# MineSweepers2019-Board.net
KiCad netlist of a schematic drawn in EAGLE
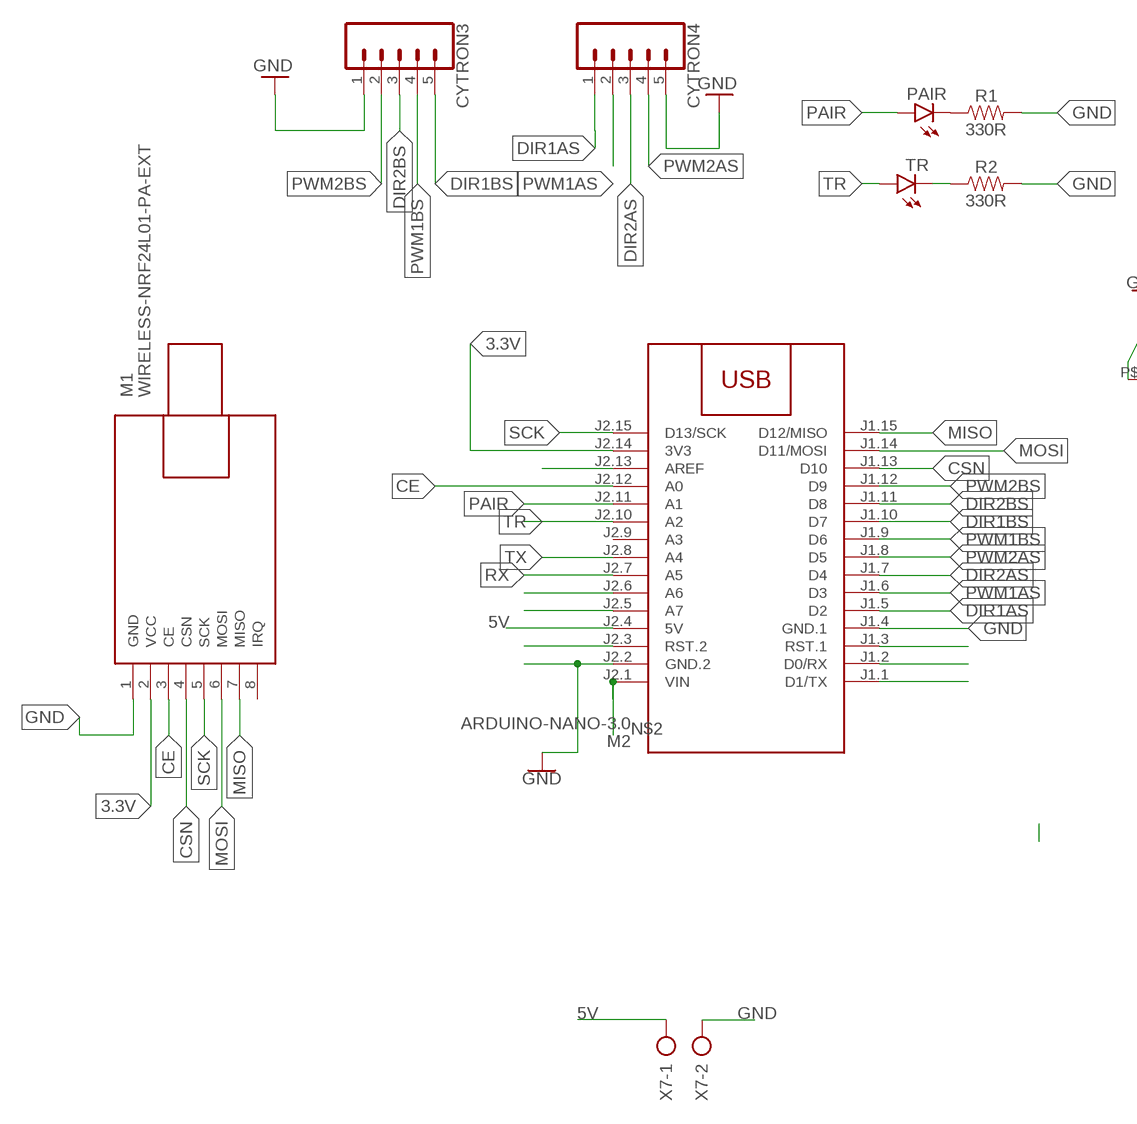
[diagram p0: schematic, sheet 1, part 1 of 2]
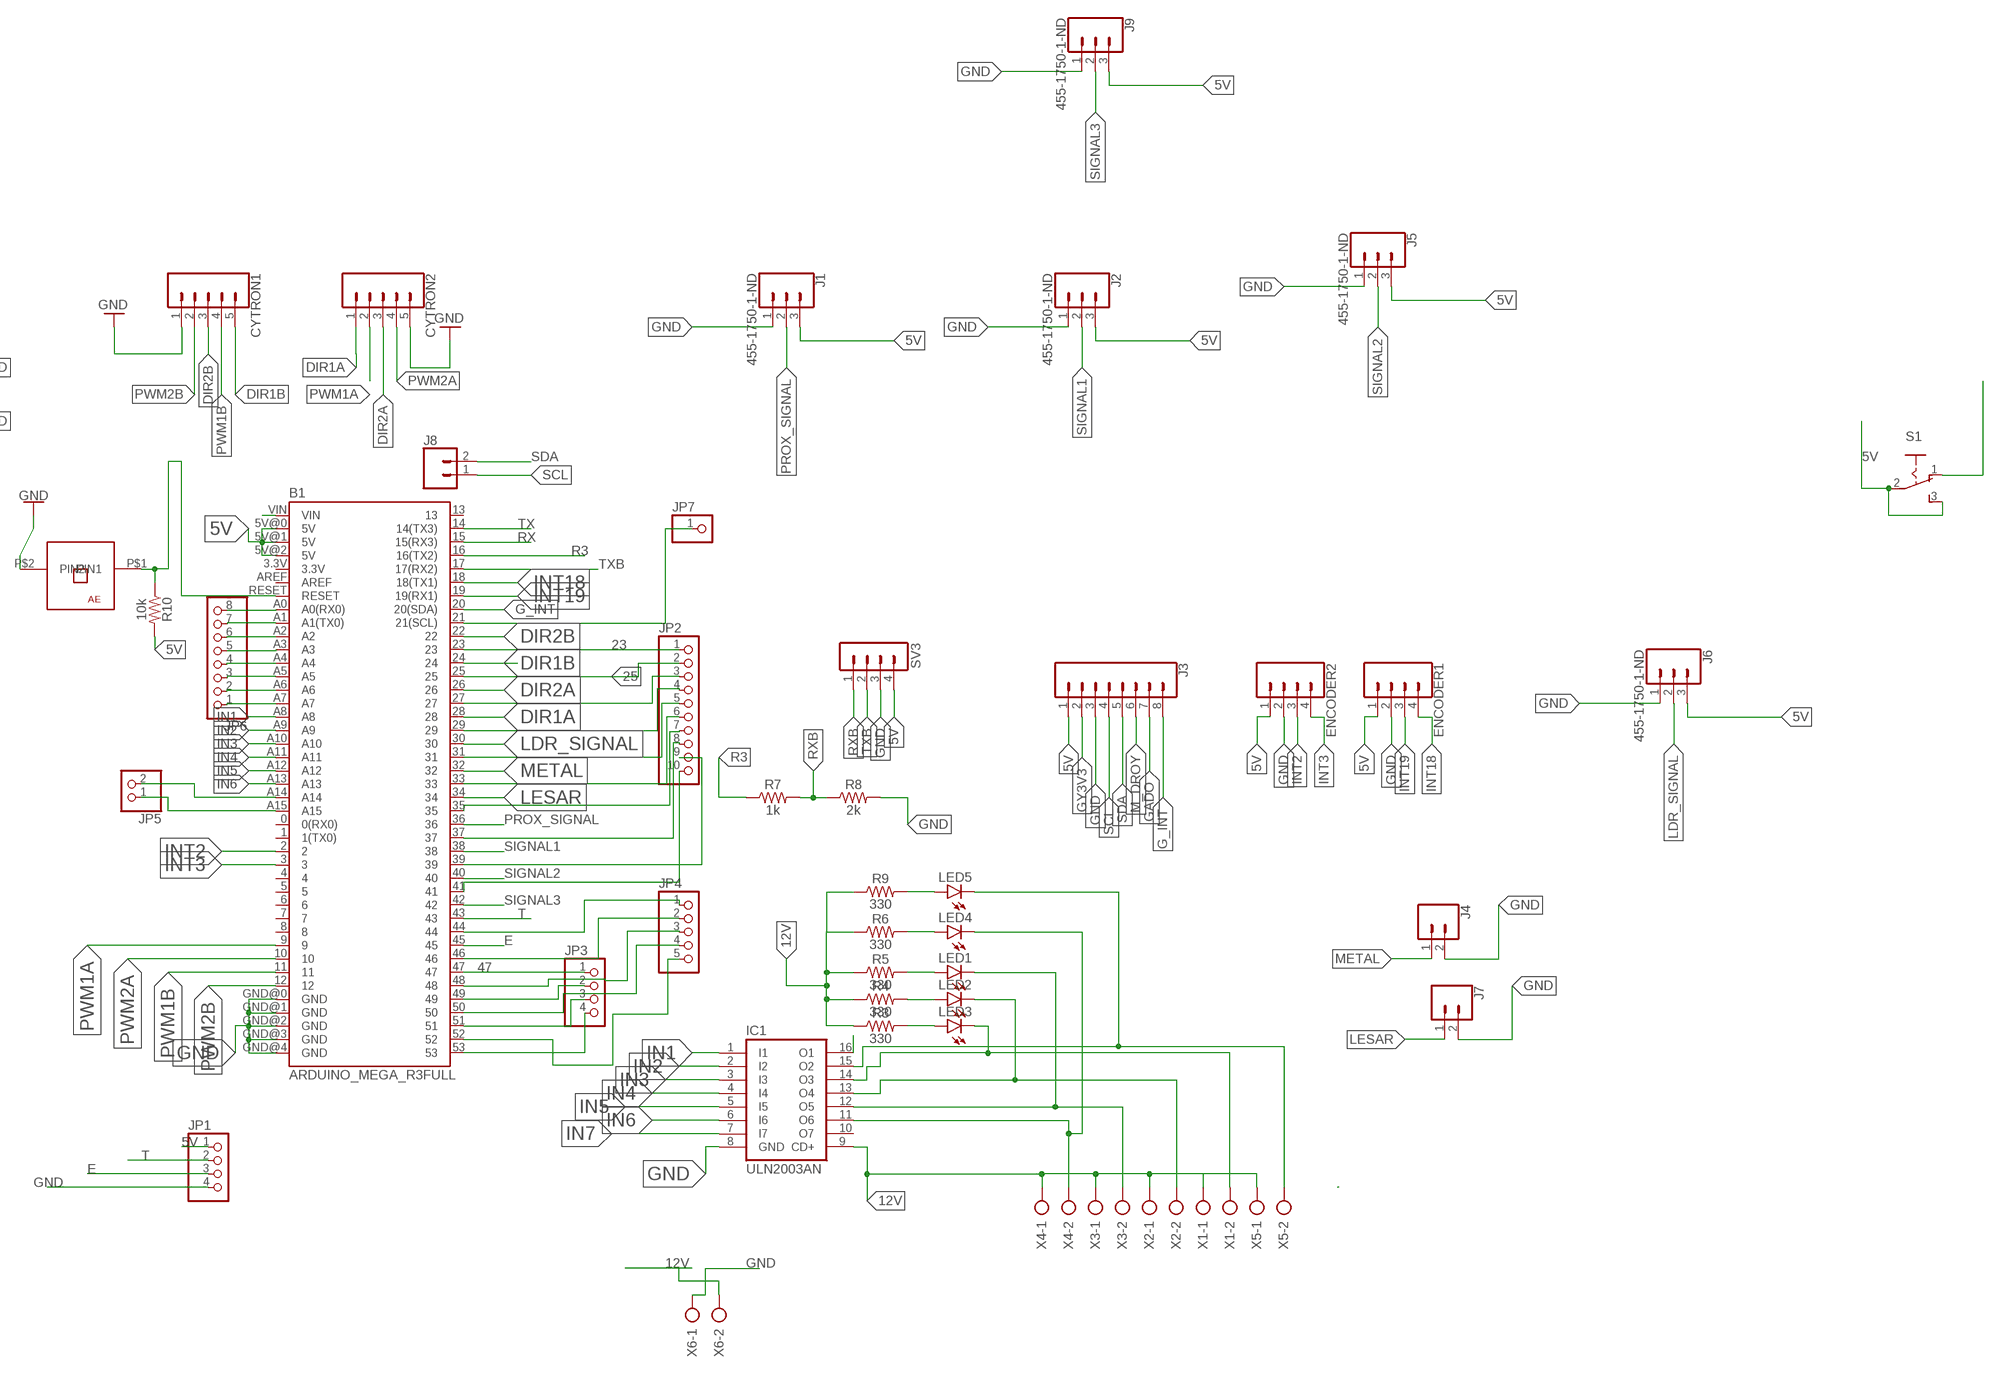
[diagram p1: schematic, sheet 1, part 2 of 2]

(export (version "E")
  (design (tool "Eeschema 10.0.6"))
  (components
    (comp (ref "B1")
      (value "ARDUINO_MEGA_R3FULL")
      (footprint "eagle-import:ARDUINO_MEGA")
      (libsource (lib "eagle-import") (part "ARDUINO_MEGA_R3FULL"))
    )
    (comp (ref "CYTRON1")
      (value "CONN_05")
      (footprint "eagle-import:1X05")
      (libsource (lib "eagle-import") (part "CONN_05"))
    )
    (comp (ref "CYTRON2")
      (value "CONN_05")
      (footprint "eagle-import:1X05")
      (libsource (lib "eagle-import") (part "CONN_05"))
    )
    (comp (ref "CYTRON3")
      (value "CONN_05")
      (footprint "eagle-import:1X05")
      (libsource (lib "eagle-import") (part "CONN_05"))
    )
    (comp (ref "CYTRON4")
      (value "CONN_05")
      (footprint "eagle-import:1X05")
      (libsource (lib "eagle-import") (part "CONN_05"))
    )
    (comp (ref "ENCODER1")
      (value "CONN_04")
      (footprint "eagle-import:1X04")
      (libsource (lib "eagle-import") (part "CONN_04"))
    )
    (comp (ref "ENCODER2")
      (value "CONN_04")
      (footprint "eagle-import:1X04")
      (libsource (lib "eagle-import") (part "CONN_04"))
    )
    (comp (ref "IC1")
      (value "ULN2003AN")
      (footprint "eagle-import:DIL16")
      (libsource (lib "eagle-import") (part "ULN2003AN"))
    )
    (comp (ref "J1")
      (value "455-1750-1-ND")
      (footprint "eagle-import:1X03")
      (libsource (lib "eagle-import") (part "CONN_03"))
    )
    (comp (ref "J2")
      (value "455-1750-1-ND")
      (footprint "eagle-import:1X03")
      (libsource (lib "eagle-import") (part "CONN_03"))
    )
    (comp (ref "J3")
      (value "CONN_08\"")
      (footprint "eagle-import:1X08")
      (libsource (lib "eagle-import") (part "CONN_08{dblquote}"))
    )
    (comp (ref "J4")
      (value "CONN_02")
      (footprint "eagle-import:1X02")
      (libsource (lib "eagle-import") (part "CONN_02"))
    )
    (comp (ref "J5")
      (value "455-1750-1-ND")
      (footprint "eagle-import:1X03")
      (libsource (lib "eagle-import") (part "CONN_03"))
    )
    (comp (ref "J6")
      (value "455-1750-1-ND")
      (footprint "eagle-import:1X03")
      (libsource (lib "eagle-import") (part "CONN_03"))
    )
    (comp (ref "J7")
      (value "CONN_02")
      (footprint "eagle-import:1X02")
      (libsource (lib "eagle-import") (part "CONN_02"))
    )
    (comp (ref "J8")
      (value "CONN_02")
      (footprint "eagle-import:1X02")
      (libsource (lib "eagle-import") (part "CONN_02"))
    )
    (comp (ref "J9")
      (value "455-1750-1-ND")
      (footprint "eagle-import:1X03")
      (libsource (lib "eagle-import") (part "CONN_03"))
    )
    (comp (ref "JP1")
      (value "PINHD-1X4")
      (footprint "eagle-import:1X04")
      (libsource (lib "eagle-import") (part "PINHD-1X4"))
    )
    (comp (ref "JP2")
      (value "PINHD-1X10")
      (footprint "eagle-import:1X10")
      (libsource (lib "eagle-import") (part "PINHD-1X10"))
    )
    (comp (ref "JP3")
      (value "PINHD-1X4")
      (footprint "eagle-import:1X04")
      (libsource (lib "eagle-import") (part "PINHD-1X4"))
    )
    (comp (ref "JP4")
      (value "PINHD-1X5")
      (footprint "eagle-import:1X05")
      (libsource (lib "eagle-import") (part "PINHD-1X5"))
    )
    (comp (ref "JP5")
      (value "PINHD-1X2")
      (footprint "eagle-import:1X02")
      (libsource (lib "eagle-import") (part "PINHD-1X2"))
    )
    (comp (ref "JP6")
      (value "PINHD-1X8")
      (footprint "eagle-import:1X08")
      (libsource (lib "eagle-import") (part "PINHD-1X8"))
    )
    (comp (ref "JP7")
      (value "PINHD-1X1")
      (footprint "eagle-import:1X01")
      (libsource (lib "eagle-import") (part "PINHD-1X1"))
    )
    (comp (ref "LED1")
      (value "LED3MM")
      (footprint "eagle-import:LED3MM")
      (libsource (lib "eagle-import") (part "LED3MM"))
    )
    (comp (ref "LED2")
      (value "LED3MM")
      (footprint "eagle-import:LED3MM")
      (libsource (lib "eagle-import") (part "LED3MM"))
    )
    (comp (ref "LED3")
      (value "LED3MM")
      (footprint "eagle-import:LED3MM")
      (libsource (lib "eagle-import") (part "LED3MM"))
    )
    (comp (ref "LED4")
      (value "LED3MM")
      (footprint "eagle-import:LED3MM")
      (libsource (lib "eagle-import") (part "LED3MM"))
    )
    (comp (ref "LED5")
      (value "LED3MM")
      (footprint "eagle-import:LED3MM")
      (libsource (lib "eagle-import") (part "LED3MM"))
    )
    (comp (ref "M1")
      (value "WIRELESS-NRF24L01-PA-EXT")
      (footprint "eagle-import:WIRELESS-NRF24L01-PA-EXT")
      (libsource (lib "eagle-import") (part "WIRELESS-NRF24L01-PA-EXT"))
    )
    (comp (ref "M2")
      (value "ARDUINO-NANO-3.0")
      (footprint "eagle-import:ARDUINO-NANO-3.0")
      (libsource (lib "eagle-import") (part "ARDUINO-NANO-3.0"))
    )
    (comp (ref "PAIR")
      (value "LED3MM")
      (footprint "eagle-import:LED3MM")
      (libsource (lib "eagle-import") (part "LED3MM"))
    )
    (comp (ref "R1")
      (value "330R")
      (footprint "eagle-import:AXIAL-0.3")
      (libsource (lib "eagle-import") (part "10MOHM-HORIZ-1/4W-5%"))
    )
    (comp (ref "R2")
      (value "330R")
      (footprint "eagle-import:AXIAL-0.3")
      (libsource (lib "eagle-import") (part "10MOHM-HORIZ-1/4W-5%"))
    )
    (comp (ref "R3")
      (value "330")
      (footprint "eagle-import:AXIAL-0.3")
      (libsource (lib "eagle-import") (part "10MOHM-HORIZ-1/4W-5%"))
    )
    (comp (ref "R4")
      (value "330")
      (footprint "eagle-import:AXIAL-0.3")
      (libsource (lib "eagle-import") (part "10MOHM-HORIZ-1/4W-5%"))
    )
    (comp (ref "R5")
      (value "330")
      (footprint "eagle-import:AXIAL-0.3")
      (libsource (lib "eagle-import") (part "10MOHM-HORIZ-1/4W-5%"))
    )
    (comp (ref "R6")
      (value "330")
      (footprint "eagle-import:AXIAL-0.3")
      (libsource (lib "eagle-import") (part "10MOHM-HORIZ-1/4W-5%"))
    )
    (comp (ref "R7")
      (value "1k")
      (footprint "eagle-import:AXIAL-0.3")
      (libsource (lib "eagle-import") (part "10MOHM-HORIZ-1/4W-5%"))
    )
    (comp (ref "R8")
      (value "2k")
      (footprint "eagle-import:AXIAL-0.3")
      (libsource (lib "eagle-import") (part "10MOHM-HORIZ-1/4W-5%"))
    )
    (comp (ref "R9")
      (value "330")
      (footprint "eagle-import:AXIAL-0.3")
      (libsource (lib "eagle-import") (part "10MOHM-HORIZ-1/4W-5%"))
    )
    (comp (ref "R10")
      (value "10k")
      (footprint "eagle-import:AXIAL-0.3")
      (libsource (lib "eagle-import") (part "10MOHM-HORIZ-1/4W-5%"))
    )
    (comp (ref "S1")
      (value "255SB")
      (footprint "eagle-import:255SB")
      (libsource (lib "eagle-import") (part "255SB"))
    )
    (comp (ref "SV3")
      (value "MA04-1")
      (footprint "eagle-import:MA04-1")
      (libsource (lib "eagle-import") (part "MA04-1"))
    )
    (comp (ref "TR")
      (value "LED3MM")
      (footprint "eagle-import:LED3MM")
      (libsource (lib "eagle-import") (part "LED3MM"))
    )
    (comp (ref "U$1")
      (value "PUSHBUTTON-AE")
      (footprint "eagle-import:PUSHBUTTON-AE")
      (libsource (lib "eagle-import") (part "PUSHBUTTON-AE"))
    )
    (comp (ref "X1")
      (value "AK500/2-H")
      (footprint "eagle-import:AK500_2-H")
      (libsource (lib "eagle-import") (part "AK500/2-H"))
    )
    (comp (ref "X2")
      (value "AK500/2-H")
      (footprint "eagle-import:AK500_2-H")
      (libsource (lib "eagle-import") (part "AK500/2-H"))
    )
    (comp (ref "X3")
      (value "AK500/2-H")
      (footprint "eagle-import:AK500_2-H")
      (libsource (lib "eagle-import") (part "AK500/2-H"))
    )
    (comp (ref "X4")
      (value "AK500/2-H")
      (footprint "eagle-import:AK500_2-H")
      (libsource (lib "eagle-import") (part "AK500/2-H"))
    )
    (comp (ref "X5")
      (value "AK500/2-H")
      (footprint "eagle-import:AK500_2-H")
      (libsource (lib "eagle-import") (part "AK500/2-H"))
    )
    (comp (ref "X6")
      (value "AK500/2-H")
      (footprint "eagle-import:AK500_2-H")
      (libsource (lib "eagle-import") (part "AK500/2-H"))
    )
    (comp (ref "X7")
      (value "AK500/2-H")
      (footprint "eagle-import:AK500_2-H")
      (libsource (lib "eagle-import") (part "AK500/2-H"))
    )
  )
  (nets
    (net (code "1") (name "/23") (class "Default")
      (node (ref "B1") (pin "23") (pinfunction "23_23") (pintype "bidirectional"))
      (node (ref "JP2") (pin "1") (pinfunction "1_1") (pintype "passive"))
    )
    (net (code "2") (name "/47") (class "Default")
      (node (ref "B1") (pin "47") (pinfunction "47_47") (pintype "bidirectional"))
      (node (ref "JP3") (pin "1") (pinfunction "1_1") (pintype "passive"))
    )
    (net (code "3") (name "/E") (class "Default")
      (node (ref "B1") (pin "45") (pinfunction "45_45") (pintype "bidirectional"))
      (node (ref "JP1") (pin "3") (pinfunction "3_3") (pintype "passive"))
    )
    (net (code "4") (name "/N$2") (class "Default")
      (node (ref "M2") (pin "J2.1") (pinfunction "VIN_J2.1") (pintype "power_in"))
    )
    (net (code "5") (name "/T") (class "Default")
      (node (ref "B1") (pin "43") (pinfunction "43_43") (pintype "bidirectional"))
      (node (ref "JP1") (pin "2") (pinfunction "2_2") (pintype "passive"))
    )
    (net (code "6") (name "3.3V") (class "Default")
      (node (ref "M1") (pin "2") (pinfunction "VCC_2") (pintype "power_in"))
      (node (ref "M2") (pin "J2.14") (pinfunction "3V3_J2.14") (pintype "power_in"))
    )
    (net (code "7") (name "5V") (class "Default")
      (node (ref "B1") (pin "5V@0") (pinfunction "5V_5V@0") (pintype "bidirectional"))
      (node (ref "B1") (pin "5V@1") (pinfunction "5V_5V@1") (pintype "bidirectional"))
      (node (ref "B1") (pin "5V@2") (pinfunction "5V_5V@2") (pintype "bidirectional"))
      (node (ref "ENCODER1") (pin "1") (pinfunction "1_1") (pintype "passive"))
      (node (ref "ENCODER2") (pin "1") (pinfunction "1_1") (pintype "passive"))
      (node (ref "J1") (pin "3") (pinfunction "3_3") (pintype "passive"))
      (node (ref "J2") (pin "3") (pinfunction "3_3") (pintype "passive"))
      (node (ref "J3") (pin "1") (pinfunction "1_1") (pintype "passive"))
      (node (ref "J5") (pin "3") (pinfunction "3_3") (pintype "passive"))
      (node (ref "J6") (pin "3") (pinfunction "3_3") (pintype "passive"))
      (node (ref "J9") (pin "3") (pinfunction "3_3") (pintype "passive"))
      (node (ref "JP1") (pin "1") (pinfunction "1_1") (pintype "passive"))
      (node (ref "M2") (pin "J2.4") (pinfunction "5V_J2.4") (pintype "power_in"))
      (node (ref "R10") (pin "P$2") (pinfunction "2_P$2") (pintype "passive"))
      (node (ref "S1") (pin "2") (pinfunction "P_2") (pintype "passive"))
      (node (ref "S1") (pin "3") (pinfunction "S_3") (pintype "passive"))
      (node (ref "SV3") (pin "4") (pinfunction "4_4") (pintype "passive"))
      (node (ref "X7") (pin "1") (pinfunction "KL_1") (pintype "passive"))
    )
    (net (code "8") (name "12V") (class "Default")
      (node (ref "IC1") (pin "9") (pinfunction "CD+_9") (pintype "passive"))
      (node (ref "R3") (pin "P$1") (pinfunction "1_P$1") (pintype "passive"))
      (node (ref "R4") (pin "P$1") (pinfunction "1_P$1") (pintype "passive"))
      (node (ref "R5") (pin "P$1") (pinfunction "1_P$1") (pintype "passive"))
      (node (ref "R6") (pin "P$1") (pinfunction "1_P$1") (pintype "passive"))
      (node (ref "R9") (pin "P$1") (pinfunction "1_P$1") (pintype "passive"))
      (node (ref "X1") (pin "1") (pinfunction "KL_1") (pintype "passive"))
      (node (ref "X2") (pin "1") (pinfunction "KL_1") (pintype "passive"))
      (node (ref "X3") (pin "1") (pinfunction "KL_1") (pintype "passive"))
      (node (ref "X4") (pin "1") (pinfunction "KL_1") (pintype "passive"))
      (node (ref "X5") (pin "1") (pinfunction "KL_1") (pintype "passive"))
      (node (ref "X6") (pin "2") (pinfunction "KL_2") (pintype "passive"))
    )
    (net (code "9") (name "25") (class "Default")
      (node (ref "B1") (pin "25") (pinfunction "25_25") (pintype "bidirectional"))
      (node (ref "JP2") (pin "2") (pinfunction "2_2") (pintype "passive"))
    )
    (net (code "10") (name "CE") (class "Default")
      (node (ref "M1") (pin "3") (pinfunction "CE_3") (pintype "bidirectional"))
      (node (ref "M2") (pin "J2.12") (pinfunction "A0_J2.12") (pintype "bidirectional"))
    )
    (net (code "11") (name "CSN") (class "Default")
      (node (ref "M1") (pin "4") (pinfunction "CSN_4") (pintype "bidirectional"))
      (node (ref "M2") (pin "J1.13") (pinfunction "D10_J1.13") (pintype "bidirectional"))
    )
    (net (code "12") (name "DIR1A") (class "Default")
      (node (ref "B1") (pin "28") (pinfunction "28_28") (pintype "bidirectional"))
      (node (ref "CYTRON2") (pin "1") (pinfunction "1_1") (pintype "passive"))
    )
    (net (code "13") (name "DIR1AS") (class "Default")
      (node (ref "CYTRON4") (pin "1") (pinfunction "1_1") (pintype "passive"))
      (node (ref "M2") (pin "J1.5") (pinfunction "D2_J1.5") (pintype "bidirectional"))
    )
    (net (code "14") (name "DIR1B") (class "Default")
      (node (ref "B1") (pin "24") (pinfunction "24_24") (pintype "bidirectional"))
      (node (ref "CYTRON1") (pin "5") (pinfunction "5_5") (pintype "passive"))
    )
    (net (code "15") (name "DIR1BS") (class "Default")
      (node (ref "CYTRON3") (pin "5") (pinfunction "5_5") (pintype "passive"))
      (node (ref "M2") (pin "J1.10") (pinfunction "D7_J1.10") (pintype "bidirectional"))
    )
    (net (code "16") (name "DIR2A") (class "Default")
      (node (ref "B1") (pin "26") (pinfunction "26_26") (pintype "bidirectional"))
      (node (ref "CYTRON2") (pin "3") (pinfunction "3_3") (pintype "passive"))
    )
    (net (code "17") (name "DIR2AS") (class "Default")
      (node (ref "CYTRON4") (pin "3") (pinfunction "3_3") (pintype "passive"))
      (node (ref "M2") (pin "J1.7") (pinfunction "D4_J1.7") (pintype "bidirectional"))
    )
    (net (code "18") (name "DIR2B") (class "Default")
      (node (ref "B1") (pin "22") (pinfunction "22_22") (pintype "bidirectional"))
      (node (ref "CYTRON1") (pin "3") (pinfunction "3_3") (pintype "passive"))
    )
    (net (code "19") (name "DIR2BS") (class "Default")
      (node (ref "CYTRON3") (pin "3") (pinfunction "3_3") (pintype "passive"))
      (node (ref "M2") (pin "J1.11") (pinfunction "D8_J1.11") (pintype "bidirectional"))
    )
    (net (code "20") (name "GADO") (class "Default")
      (node (ref "J3") (pin "7") (pinfunction "7_7") (pintype "passive"))
    )
    (net (code "21") (name "GND") (class "Default")
      (node (ref "B1") (pin "GND@0") (pinfunction "GND_GND@0") (pintype "bidirectional"))
      (node (ref "B1") (pin "GND@1") (pinfunction "GND_GND@1") (pintype "bidirectional"))
      (node (ref "B1") (pin "GND@2") (pinfunction "GND_GND@2") (pintype "bidirectional"))
      (node (ref "B1") (pin "GND@3") (pinfunction "GND_GND@3") (pintype "bidirectional"))
      (node (ref "B1") (pin "GND@4") (pinfunction "GND_GND@4") (pintype "bidirectional"))
      (node (ref "CYTRON1") (pin "1") (pinfunction "1_1") (pintype "passive"))
      (node (ref "CYTRON2") (pin "5") (pinfunction "5_5") (pintype "passive"))
      (node (ref "CYTRON3") (pin "1") (pinfunction "1_1") (pintype "passive"))
      (node (ref "CYTRON4") (pin "5") (pinfunction "5_5") (pintype "passive"))
      (node (ref "ENCODER1") (pin "2") (pinfunction "2_2") (pintype "passive"))
      (node (ref "ENCODER2") (pin "2") (pinfunction "2_2") (pintype "passive"))
      (node (ref "IC1") (pin "8") (pinfunction "GND_8") (pintype "power_in"))
      (node (ref "J1") (pin "1") (pinfunction "1_1") (pintype "passive"))
      (node (ref "J2") (pin "1") (pinfunction "1_1") (pintype "passive"))
      (node (ref "J3") (pin "3") (pinfunction "3_3") (pintype "passive"))
      (node (ref "J4") (pin "2") (pinfunction "2_2") (pintype "passive"))
      (node (ref "J5") (pin "1") (pinfunction "1_1") (pintype "passive"))
      (node (ref "J6") (pin "1") (pinfunction "1_1") (pintype "passive"))
      (node (ref "J7") (pin "2") (pinfunction "2_2") (pintype "passive"))
      (node (ref "J9") (pin "1") (pinfunction "1_1") (pintype "passive"))
      (node (ref "JP1") (pin "4") (pinfunction "4_4") (pintype "passive"))
      (node (ref "M1") (pin "1") (pinfunction "GND_1") (pintype "power_in"))
      (node (ref "M2") (pin "J1.4") (pinfunction "GND.1_J1.4") (pintype "power_in"))
      (node (ref "M2") (pin "J2.2") (pinfunction "GND.2_J2.2") (pintype "power_in"))
      (node (ref "R1") (pin "P$2") (pinfunction "2_P$2") (pintype "passive"))
      (node (ref "R2") (pin "P$2") (pinfunction "2_P$2") (pintype "passive"))
      (node (ref "R8") (pin "P$2") (pinfunction "2_P$2") (pintype "passive"))
      (node (ref "SV3") (pin "3") (pinfunction "3_3") (pintype "passive"))
      (node (ref "U$1") (pin "P$2") (pinfunction "PIN2_P$2") (pintype "bidirectional"))
      (node (ref "X6") (pin "1") (pinfunction "KL_1") (pintype "passive"))
      (node (ref "X7") (pin "2") (pinfunction "KL_2") (pintype "passive"))
    )
    (net (code "22") (name "GY3V3") (class "Default")
      (node (ref "J3") (pin "2") (pinfunction "2_2") (pintype "passive"))
    )
    (net (code "23") (name "G_INT") (class "Default")
      (node (ref "B1") (pin "20") (pinfunction "20(SDA)_20") (pintype "bidirectional"))
      (node (ref "J3") (pin "8") (pinfunction "8_8") (pintype "passive"))
    )
    (net (code "24") (name "IN1") (class "Default")
      (node (ref "B1") (pin "A8") (pinfunction "A8_A8") (pintype "bidirectional"))
      (node (ref "IC1") (pin "1") (pinfunction "I1_1") (pintype "input"))
    )
    (net (code "25") (name "IN2") (class "Default")
      (node (ref "B1") (pin "A9") (pinfunction "A9_A9") (pintype "bidirectional"))
      (node (ref "IC1") (pin "2") (pinfunction "I2_2") (pintype "input"))
    )
    (net (code "26") (name "IN3") (class "Default")
      (node (ref "B1") (pin "A10") (pinfunction "A10_A10") (pintype "bidirectional"))
      (node (ref "IC1") (pin "3") (pinfunction "I3_3") (pintype "input"))
    )
    (net (code "27") (name "IN4") (class "Default")
      (node (ref "B1") (pin "A11") (pinfunction "A11_A11") (pintype "bidirectional"))
      (node (ref "IC1") (pin "4") (pinfunction "I4_4") (pintype "input"))
    )
    (net (code "28") (name "IN5") (class "Default")
      (node (ref "B1") (pin "A12") (pinfunction "A12_A12") (pintype "bidirectional"))
      (node (ref "IC1") (pin "5") (pinfunction "I5_5") (pintype "input"))
    )
    (net (code "29") (name "IN6") (class "Default")
      (node (ref "B1") (pin "A13") (pinfunction "A13_A13") (pintype "bidirectional"))
      (node (ref "IC1") (pin "6") (pinfunction "I6_6") (pintype "input"))
    )
    (net (code "30") (name "IN7") (class "Default")
      (node (ref "IC1") (pin "7") (pinfunction "I7_7") (pintype "input"))
    )
    (net (code "31") (name "INT2") (class "Default")
      (node (ref "B1") (pin "2") (pinfunction "2_2") (pintype "bidirectional"))
      (node (ref "ENCODER2") (pin "3") (pinfunction "3_3") (pintype "passive"))
    )
    (net (code "32") (name "INT3") (class "Default")
      (node (ref "B1") (pin "3") (pinfunction "3_3") (pintype "bidirectional"))
      (node (ref "ENCODER2") (pin "4") (pinfunction "4_4") (pintype "passive"))
    )
    (net (code "33") (name "INT18") (class "Default")
      (node (ref "B1") (pin "18") (pinfunction "18(TX1)_18") (pintype "bidirectional"))
      (node (ref "ENCODER1") (pin "4") (pinfunction "4_4") (pintype "passive"))
    )
    (net (code "34") (name "INT19") (class "Default")
      (node (ref "B1") (pin "19") (pinfunction "19(RX1)_19") (pintype "bidirectional"))
      (node (ref "ENCODER1") (pin "3") (pinfunction "3_3") (pintype "passive"))
    )
    (net (code "35") (name "LDR_SIGNAL") (class "Default")
      (node (ref "B1") (pin "30") (pinfunction "30_30") (pintype "bidirectional"))
      (node (ref "J6") (pin "2") (pinfunction "2_2") (pintype "passive"))
    )
    (net (code "36") (name "LESAR") (class "Default")
      (node (ref "B1") (pin "34") (pinfunction "34_34") (pintype "bidirectional"))
      (node (ref "J7") (pin "1") (pinfunction "1_1") (pintype "passive"))
    )
    (net (code "37") (name "METAL") (class "Default")
      (node (ref "B1") (pin "32") (pinfunction "32_32") (pintype "bidirectional"))
      (node (ref "J4") (pin "1") (pinfunction "1_1") (pintype "passive"))
    )
    (net (code "38") (name "MISO") (class "Default")
      (node (ref "M1") (pin "7") (pinfunction "MISO_7") (pintype "bidirectional"))
      (node (ref "M2") (pin "J1.15") (pinfunction "D12/MISO_J1.15") (pintype "bidirectional"))
    )
    (net (code "39") (name "MOSI") (class "Default")
      (node (ref "M1") (pin "6") (pinfunction "MOSI_6") (pintype "bidirectional"))
      (node (ref "M2") (pin "J1.14") (pinfunction "D11/MOSI_J1.14") (pintype "bidirectional"))
    )
    (net (code "40") (name "M_DROY") (class "Default")
      (node (ref "J3") (pin "6") (pinfunction "6_6") (pintype "passive"))
    )
    (net (code "41") (name "Net-(B1-21(SCL))") (class "Default")
      (node (ref "B1") (pin "21") (pinfunction "21(SCL)_21") (pintype "bidirectional"))
      (node (ref "JP7") (pin "1") (pinfunction "1_1") (pintype "passive"))
    )
    (net (code "42") (name "Net-(B1-A0(RX0))") (class "Default")
      (node (ref "B1") (pin "A0") (pinfunction "A0(RX0)_A0") (pintype "bidirectional"))
      (node (ref "JP6") (pin "8") (pinfunction "8_8") (pintype "passive"))
    )
    (net (code "43") (name "Net-(B1-A1(TX0))") (class "Default")
      (node (ref "B1") (pin "A1") (pinfunction "A1(TX0)_A1") (pintype "bidirectional"))
      (node (ref "JP6") (pin "7") (pinfunction "7_7") (pintype "passive"))
    )
    (net (code "44") (name "Net-(B1-Pad27)") (class "Default")
      (node (ref "B1") (pin "27") (pinfunction "27_27") (pintype "bidirectional"))
      (node (ref "JP2") (pin "3") (pinfunction "3_3") (pintype "passive"))
    )
    (net (code "45") (name "Net-(B1-Pad29)") (class "Default")
      (node (ref "B1") (pin "29") (pinfunction "29_29") (pintype "bidirectional"))
      (node (ref "JP2") (pin "4") (pinfunction "4_4") (pintype "passive"))
    )
    (net (code "46") (name "Net-(B1-Pad31)") (class "Default")
      (node (ref "B1") (pin "31") (pinfunction "31_31") (pintype "bidirectional"))
      (node (ref "JP2") (pin "5") (pinfunction "5_5") (pintype "passive"))
    )
    (net (code "47") (name "Net-(B1-Pad33)") (class "Default")
      (node (ref "B1") (pin "33") (pinfunction "33_33") (pintype "bidirectional"))
      (node (ref "JP2") (pin "6") (pinfunction "6_6") (pintype "passive"))
    )
    (net (code "48") (name "Net-(B1-Pad35)") (class "Default")
      (node (ref "B1") (pin "35") (pinfunction "35_35") (pintype "bidirectional"))
      (node (ref "JP2") (pin "7") (pinfunction "7_7") (pintype "passive"))
    )
    (net (code "49") (name "Net-(B1-Pad37)") (class "Default")
      (node (ref "B1") (pin "37") (pinfunction "37_37") (pintype "bidirectional"))
      (node (ref "JP2") (pin "8") (pinfunction "8_8") (pintype "passive"))
    )
    (net (code "50") (name "Net-(B1-Pad39)") (class "Default")
      (node (ref "B1") (pin "39") (pinfunction "39_39") (pintype "bidirectional"))
      (node (ref "JP2") (pin "9") (pinfunction "9_9") (pintype "passive"))
    )
    (net (code "51") (name "Net-(B1-Pad41)") (class "Default")
      (node (ref "B1") (pin "41") (pinfunction "41_41") (pintype "bidirectional"))
      (node (ref "JP2") (pin "10") (pinfunction "10_10") (pintype "passive"))
    )
    (net (code "52") (name "Net-(B1-Pad44)") (class "Default")
      (node (ref "B1") (pin "44") (pinfunction "44_44") (pintype "bidirectional"))
      (node (ref "JP4") (pin "1") (pinfunction "1_1") (pintype "passive"))
    )
    (net (code "53") (name "Net-(B1-Pad46)") (class "Default")
      (node (ref "B1") (pin "46") (pinfunction "46_46") (pintype "bidirectional"))
      (node (ref "JP4") (pin "2") (pinfunction "2_2") (pintype "passive"))
    )
    (net (code "54") (name "Net-(B1-Pad48)") (class "Default")
      (node (ref "B1") (pin "48") (pinfunction "48_48") (pintype "bidirectional"))
      (node (ref "JP4") (pin "3") (pinfunction "3_3") (pintype "passive"))
    )
    (net (code "55") (name "Net-(B1-Pad49)") (class "Default")
      (node (ref "B1") (pin "49") (pinfunction "49_49") (pintype "bidirectional"))
      (node (ref "JP3") (pin "2") (pinfunction "2_2") (pintype "passive"))
    )
    (net (code "56") (name "Net-(B1-Pad50)") (class "Default")
      (node (ref "B1") (pin "50") (pinfunction "50_50") (pintype "bidirectional"))
      (node (ref "JP4") (pin "4") (pinfunction "4_4") (pintype "passive"))
    )
    (net (code "57") (name "Net-(B1-Pad51)") (class "Default")
      (node (ref "B1") (pin "51") (pinfunction "51_51") (pintype "bidirectional"))
      (node (ref "JP3") (pin "3") (pinfunction "3_3") (pintype "passive"))
    )
    (net (code "58") (name "Net-(B1-Pad52)") (class "Default")
      (node (ref "B1") (pin "52") (pinfunction "52_52") (pintype "bidirectional"))
      (node (ref "JP4") (pin "5") (pinfunction "5_5") (pintype "passive"))
    )
    (net (code "59") (name "Net-(B1-Pad53)") (class "Default")
      (node (ref "B1") (pin "53") (pinfunction "53_53") (pintype "bidirectional"))
      (node (ref "JP3") (pin "4") (pinfunction "4_4") (pintype "passive"))
    )
    (net (code "60") (name "Net-(B1-PadA2)") (class "Default")
      (node (ref "B1") (pin "A2") (pinfunction "A2_A2") (pintype "bidirectional"))
      (node (ref "JP6") (pin "6") (pinfunction "6_6") (pintype "passive"))
    )
    (net (code "61") (name "Net-(B1-PadA3)") (class "Default")
      (node (ref "B1") (pin "A3") (pinfunction "A3_A3") (pintype "bidirectional"))
      (node (ref "JP6") (pin "5") (pinfunction "5_5") (pintype "passive"))
    )
    (net (code "62") (name "Net-(B1-PadA4)") (class "Default")
      (node (ref "B1") (pin "A4") (pinfunction "A4_A4") (pintype "bidirectional"))
      (node (ref "JP6") (pin "4") (pinfunction "4_4") (pintype "passive"))
    )
    (net (code "63") (name "Net-(B1-PadA5)") (class "Default")
      (node (ref "B1") (pin "A5") (pinfunction "A5_A5") (pintype "bidirectional"))
      (node (ref "JP6") (pin "3") (pinfunction "3_3") (pintype "passive"))
    )
    (net (code "64") (name "Net-(B1-PadA6)") (class "Default")
      (node (ref "B1") (pin "A6") (pinfunction "A6_A6") (pintype "bidirectional"))
      (node (ref "JP6") (pin "2") (pinfunction "2_2") (pintype "passive"))
    )
    (net (code "65") (name "Net-(B1-PadA7)") (class "Default")
      (node (ref "B1") (pin "A7") (pinfunction "A7_A7") (pintype "bidirectional"))
      (node (ref "JP6") (pin "1") (pinfunction "1_1") (pintype "passive"))
    )
    (net (code "66") (name "Net-(B1-PadA14)") (class "Default")
      (node (ref "B1") (pin "A14") (pinfunction "A14_A14") (pintype "bidirectional"))
      (node (ref "JP5") (pin "2") (pinfunction "2_2") (pintype "passive"))
    )
    (net (code "67") (name "Net-(B1-PadA15)") (class "Default")
      (node (ref "B1") (pin "A15") (pinfunction "A15_A15") (pintype "bidirectional"))
      (node (ref "JP5") (pin "1") (pinfunction "1_1") (pintype "passive"))
    )
    (net (code "68") (name "Net-(IC1-O2)") (class "Default")
      (node (ref "IC1") (pin "15") (pinfunction "O2_15") (pintype "open_collector"))
      (node (ref "LED5") (pin "K") (pinfunction "C_K") (pintype "passive"))
      (node (ref "X5") (pin "2") (pinfunction "KL_2") (pintype "passive"))
    )
    (net (code "69") (name "Net-(IC1-O3)") (class "Default")
      (node (ref "IC1") (pin "14") (pinfunction "O3_14") (pintype "open_collector"))
      (node (ref "LED3") (pin "K") (pinfunction "C_K") (pintype "passive"))
      (node (ref "X1") (pin "2") (pinfunction "KL_2") (pintype "passive"))
    )
    (net (code "70") (name "Net-(IC1-O4)") (class "Default")
      (node (ref "IC1") (pin "13") (pinfunction "O4_13") (pintype "open_collector"))
      (node (ref "LED2") (pin "K") (pinfunction "C_K") (pintype "passive"))
      (node (ref "X2") (pin "2") (pinfunction "KL_2") (pintype "passive"))
    )
    (net (code "71") (name "Net-(IC1-O5)") (class "Default")
      (node (ref "IC1") (pin "12") (pinfunction "O5_12") (pintype "open_collector"))
      (node (ref "LED1") (pin "K") (pinfunction "C_K") (pintype "passive"))
      (node (ref "X3") (pin "2") (pinfunction "KL_2") (pintype "passive"))
    )
    (net (code "72") (name "Net-(IC1-O6)") (class "Default")
      (node (ref "IC1") (pin "11") (pinfunction "O6_11") (pintype "open_collector"))
      (node (ref "LED4") (pin "K") (pinfunction "C_K") (pintype "passive"))
      (node (ref "X4") (pin "2") (pinfunction "KL_2") (pintype "passive"))
    )
    (net (code "73") (name "Net-(PAIR-C)") (class "Default")
      (node (ref "PAIR") (pin "K") (pinfunction "C_K") (pintype "passive"))
      (node (ref "R1") (pin "P$1") (pinfunction "1_P$1") (pintype "passive"))
    )
    (net (code "74") (name "Net-(R2-1)") (class "Default")
      (node (ref "R2") (pin "P$1") (pinfunction "1_P$1") (pintype "passive"))
      (node (ref "TR") (pin "K") (pinfunction "C_K") (pintype "passive"))
    )
    (net (code "75") (name "Net-(R3-2)") (class "Default")
      (node (ref "LED3") (pin "A") (pinfunction "A_A") (pintype "passive"))
      (node (ref "R3") (pin "P$2") (pinfunction "2_P$2") (pintype "passive"))
    )
    (net (code "76") (name "Net-(R4-2)") (class "Default")
      (node (ref "LED2") (pin "A") (pinfunction "A_A") (pintype "passive"))
      (node (ref "R4") (pin "P$2") (pinfunction "2_P$2") (pintype "passive"))
    )
    (net (code "77") (name "Net-(R5-2)") (class "Default")
      (node (ref "LED1") (pin "A") (pinfunction "A_A") (pintype "passive"))
      (node (ref "R5") (pin "P$2") (pinfunction "2_P$2") (pintype "passive"))
    )
    (net (code "78") (name "Net-(R6-2)") (class "Default")
      (node (ref "LED4") (pin "A") (pinfunction "A_A") (pintype "passive"))
      (node (ref "R6") (pin "P$2") (pinfunction "2_P$2") (pintype "passive"))
    )
    (net (code "79") (name "Net-(R9-2)") (class "Default")
      (node (ref "LED5") (pin "A") (pinfunction "A_A") (pintype "passive"))
      (node (ref "R9") (pin "P$2") (pinfunction "2_P$2") (pintype "passive"))
    )
    (net (code "80") (name "Net-(R10-1)") (class "Default")
      (node (ref "B1") (pin "RESET") (pinfunction "RESET_RESET") (pintype "bidirectional"))
      (node (ref "R10") (pin "P$1") (pinfunction "1_P$1") (pintype "passive"))
      (node (ref "U$1") (pin "P$1") (pinfunction "PIN1_P$1") (pintype "bidirectional"))
    )
    (net (code "81") (name "PAIR") (class "Default")
      (node (ref "M2") (pin "J2.11") (pinfunction "A1_J2.11") (pintype "bidirectional"))
      (node (ref "PAIR") (pin "A") (pinfunction "A_A") (pintype "passive"))
    )
    (net (code "82") (name "PROX_SIGNAL") (class "Default")
      (node (ref "B1") (pin "36") (pinfunction "36_36") (pintype "bidirectional"))
      (node (ref "J1") (pin "2") (pinfunction "2_2") (pintype "passive"))
    )
    (net (code "83") (name "PWM1A") (class "Default")
      (node (ref "B1") (pin "9") (pinfunction "9_9") (pintype "bidirectional"))
      (node (ref "CYTRON2") (pin "2") (pinfunction "2_2") (pintype "passive"))
    )
    (net (code "84") (name "PWM1AS") (class "Default")
      (node (ref "CYTRON4") (pin "2") (pinfunction "2_2") (pintype "passive"))
      (node (ref "M2") (pin "J1.6") (pinfunction "D3_J1.6") (pintype "bidirectional"))
    )
    (net (code "85") (name "PWM1B") (class "Default")
      (node (ref "B1") (pin "11") (pinfunction "11_11") (pintype "bidirectional"))
      (node (ref "CYTRON1") (pin "4") (pinfunction "4_4") (pintype "passive"))
    )
    (net (code "86") (name "PWM1BS") (class "Default")
      (node (ref "CYTRON3") (pin "4") (pinfunction "4_4") (pintype "passive"))
      (node (ref "M2") (pin "J1.9") (pinfunction "D6_J1.9") (pintype "bidirectional"))
    )
    (net (code "87") (name "PWM2A") (class "Default")
      (node (ref "B1") (pin "10") (pinfunction "10_10") (pintype "bidirectional"))
      (node (ref "CYTRON2") (pin "4") (pinfunction "4_4") (pintype "passive"))
    )
    (net (code "88") (name "PWM2AS") (class "Default")
      (node (ref "CYTRON4") (pin "4") (pinfunction "4_4") (pintype "passive"))
      (node (ref "M2") (pin "J1.8") (pinfunction "D5_J1.8") (pintype "bidirectional"))
    )
    (net (code "89") (name "PWM2B") (class "Default")
      (node (ref "B1") (pin "12") (pinfunction "12_12") (pintype "bidirectional"))
      (node (ref "CYTRON1") (pin "2") (pinfunction "2_2") (pintype "passive"))
    )
    (net (code "90") (name "PWM2BS") (class "Default")
      (node (ref "CYTRON3") (pin "2") (pinfunction "2_2") (pintype "passive"))
      (node (ref "M2") (pin "J1.12") (pinfunction "D9_J1.12") (pintype "bidirectional"))
    )
    (net (code "91") (name "R3") (class "Default")
      (node (ref "B1") (pin "16") (pinfunction "16(TX2)_16") (pintype "bidirectional"))
      (node (ref "R7") (pin "P$1") (pinfunction "1_P$1") (pintype "passive"))
    )
    (net (code "92") (name "RX") (class "Default")
      (node (ref "B1") (pin "15") (pinfunction "15(RX3)_15") (pintype "bidirectional"))
      (node (ref "M2") (pin "J2.7") (pinfunction "A5_J2.7") (pintype "bidirectional"))
    )
    (net (code "93") (name "RXB") (class "Default")
      (node (ref "R7") (pin "P$2") (pinfunction "2_P$2") (pintype "passive"))
      (node (ref "R8") (pin "P$1") (pinfunction "1_P$1") (pintype "passive"))
      (node (ref "SV3") (pin "1") (pinfunction "1_1") (pintype "passive"))
    )
    (net (code "94") (name "SCK") (class "Default")
      (node (ref "M1") (pin "5") (pinfunction "SCK_5") (pintype "bidirectional"))
      (node (ref "M2") (pin "J2.15") (pinfunction "D13/SCK_J2.15") (pintype "bidirectional"))
    )
    (net (code "95") (name "SCL") (class "Default")
      (node (ref "J3") (pin "4") (pinfunction "4_4") (pintype "passive"))
      (node (ref "J8") (pin "1") (pinfunction "1_1") (pintype "passive"))
    )
    (net (code "96") (name "SDA") (class "Default")
      (node (ref "J3") (pin "5") (pinfunction "5_5") (pintype "passive"))
      (node (ref "J8") (pin "2") (pinfunction "2_2") (pintype "passive"))
    )
    (net (code "97") (name "SIGNAL1") (class "Default")
      (node (ref "B1") (pin "38") (pinfunction "38_38") (pintype "bidirectional"))
      (node (ref "J2") (pin "2") (pinfunction "2_2") (pintype "passive"))
    )
    (net (code "98") (name "SIGNAL2") (class "Default")
      (node (ref "B1") (pin "40") (pinfunction "40_40") (pintype "bidirectional"))
      (node (ref "J5") (pin "2") (pinfunction "2_2") (pintype "passive"))
    )
    (net (code "99") (name "SIGNAL3") (class "Default")
      (node (ref "B1") (pin "42") (pinfunction "42_42") (pintype "bidirectional"))
      (node (ref "J9") (pin "2") (pinfunction "2_2") (pintype "passive"))
    )
    (net (code "100") (name "TR") (class "Default")
      (node (ref "M2") (pin "J2.10") (pinfunction "A2_J2.10") (pintype "bidirectional"))
      (node (ref "TR") (pin "A") (pinfunction "A_A") (pintype "passive"))
    )
    (net (code "101") (name "TX") (class "Default")
      (node (ref "B1") (pin "14") (pinfunction "14(TX3)_14") (pintype "bidirectional"))
      (node (ref "M2") (pin "J2.8") (pinfunction "A4_J2.8") (pintype "bidirectional"))
    )
    (net (code "102") (name "TXB") (class "Default")
      (node (ref "B1") (pin "17") (pinfunction "17(RX2)_17") (pintype "bidirectional"))
      (node (ref "SV3") (pin "2") (pinfunction "2_2") (pintype "passive"))
    )
    (net (code "103") (name "unconnected-(B1-0(RX0)-Pad0)") (class "Default")
      (node (ref "B1") (pin "0") (pinfunction "0(RX0)_0") (pintype "bidirectional"))
    )
    (net (code "104") (name "unconnected-(B1-1(TX0)-Pad1)") (class "Default")
      (node (ref "B1") (pin "1") (pinfunction "1(TX0)_1") (pintype "bidirectional"))
    )
    (net (code "105") (name "unconnected-(B1-Pad3.3V)") (class "Default")
      (node (ref "B1") (pin "3.3V") (pinfunction "3.3V_3.3V") (pintype "bidirectional"))
    )
    (net (code "106") (name "unconnected-(B1-Pad4)") (class "Default")
      (node (ref "B1") (pin "4") (pinfunction "4_4") (pintype "bidirectional"))
    )
    (net (code "107") (name "unconnected-(B1-Pad5)") (class "Default")
      (node (ref "B1") (pin "5") (pinfunction "5_5") (pintype "bidirectional"))
    )
    (net (code "108") (name "unconnected-(B1-Pad6)") (class "Default")
      (node (ref "B1") (pin "6") (pinfunction "6_6") (pintype "bidirectional"))
    )
    (net (code "109") (name "unconnected-(B1-Pad7)") (class "Default")
      (node (ref "B1") (pin "7") (pinfunction "7_7") (pintype "bidirectional"))
    )
    (net (code "110") (name "unconnected-(B1-Pad8)") (class "Default")
      (node (ref "B1") (pin "8") (pinfunction "8_8") (pintype "bidirectional"))
    )
    (net (code "111") (name "unconnected-(B1-Pad13)") (class "Default")
      (node (ref "B1") (pin "13") (pinfunction "13_13") (pintype "bidirectional"))
    )
    (net (code "112") (name "unconnected-(B1-PadAREF)") (class "Default")
      (node (ref "B1") (pin "AREF") (pinfunction "AREF_AREF") (pintype "bidirectional"))
    )
    (net (code "113") (name "unconnected-(B1-PadVIN)") (class "Default")
      (node (ref "B1") (pin "VIN") (pinfunction "VIN_VIN") (pintype "bidirectional"))
    )
    (net (code "114") (name "unconnected-(IC1-O1-Pad16)") (class "Default")
      (node (ref "IC1") (pin "16") (pinfunction "O1_16") (pintype "open_collector"))
    )
    (net (code "115") (name "unconnected-(IC1-O7-Pad10)") (class "Default")
      (node (ref "IC1") (pin "10") (pinfunction "O7_10") (pintype "open_collector"))
    )
    (net (code "116") (name "unconnected-(M1-IRQ-Pad8)") (class "Default")
      (node (ref "M1") (pin "8") (pinfunction "IRQ_8") (pintype "bidirectional"))
    )
    (net (code "117") (name "unconnected-(M2-A3-PadJ2.9)") (class "Default")
      (node (ref "M2") (pin "J2.9") (pinfunction "A3_J2.9") (pintype "bidirectional"))
    )
    (net (code "118") (name "unconnected-(M2-A6-PadJ2.6)") (class "Default")
      (node (ref "M2") (pin "J2.6") (pinfunction "A6_J2.6") (pintype "bidirectional"))
    )
    (net (code "119") (name "unconnected-(M2-A7-PadJ2.5)") (class "Default")
      (node (ref "M2") (pin "J2.5") (pinfunction "A7_J2.5") (pintype "bidirectional"))
    )
    (net (code "120") (name "unconnected-(M2-AREF-PadJ2.13)") (class "Default")
      (node (ref "M2") (pin "J2.13") (pinfunction "AREF_J2.13") (pintype "bidirectional"))
    )
    (net (code "121") (name "unconnected-(M2-D0{slash}RX-PadJ1.2)") (class "Default")
      (node (ref "M2") (pin "J1.2") (pinfunction "D0/RX_J1.2") (pintype "bidirectional"))
    )
    (net (code "122") (name "unconnected-(M2-D1{slash}TX-PadJ1.1)") (class "Default")
      (node (ref "M2") (pin "J1.1") (pinfunction "D1/TX_J1.1") (pintype "bidirectional"))
    )
    (net (code "123") (name "unconnected-(M2-RST.1-PadJ1.3)") (class "Default")
      (node (ref "M2") (pin "J1.3") (pinfunction "RST.1_J1.3") (pintype "bidirectional"))
    )
    (net (code "124") (name "unconnected-(M2-RST.2-PadJ2.3)") (class "Default")
      (node (ref "M2") (pin "J2.3") (pinfunction "RST.2_J2.3") (pintype "bidirectional"))
    )
    (net (code "125") (name "unconnected-(S1-O-Pad1)") (class "Default")
      (node (ref "S1") (pin "1") (pinfunction "O_1") (pintype "passive"))
    )
  )
)
